# buzzer_sub_module.net
KiCad netlist of a schematic drawn in EAGLE
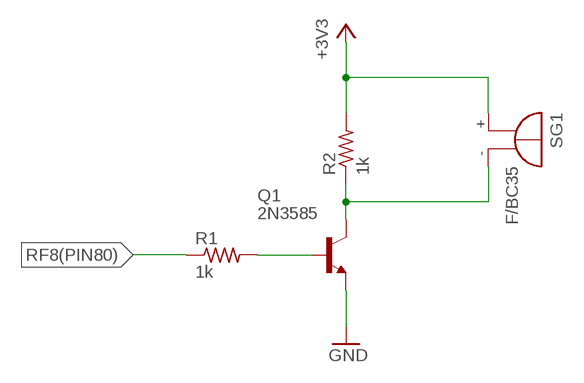
[diagram p0: schematic, sheet 1]

(export (version "E")
  (design (tool "Eeschema 10.0.6"))
  (components
    (comp (ref "Q1")
      (value "2N3585")
      (footprint "eagle-import:TO66")
      (libsource (lib "eagle-import") (part "2N3585"))
    )
    (comp (ref "R1")
      (value "1k")
      (footprint "eagle-import:0204V")
      (libsource (lib "eagle-import") (part "R-US_0204/2V"))
    )
    (comp (ref "R2")
      (value "1k")
      (footprint "eagle-import:0204V")
      (libsource (lib "eagle-import") (part "R-US_0204/2V"))
    )
    (comp (ref "SG1")
      (value "F/BC35")
      (footprint "eagle-import:F_BC35")
      (libsource (lib "eagle-import") (part "F/BC35"))
    )
  )
  (nets
    (net (code "1") (name "+3V3") (class "Default")
      (node (ref "R2") (pin "2") (pinfunction "2_2") (pintype "passive"))
      (node (ref "SG1") (pin "+") (pinfunction "+_+") (pintype "passive"))
    )
    (net (code "2") (name "GND") (class "Default")
      (node (ref "Q1") (pin "1") (pinfunction "E_1") (pintype "passive"))
    )
    (net (code "3") (name "Net-(Q1-B)") (class "Default")
      (node (ref "Q1") (pin "2") (pinfunction "B_2") (pintype "passive"))
      (node (ref "R1") (pin "2") (pinfunction "2_2") (pintype "passive"))
    )
    (net (code "4") (name "Net-(Q1-C-Pad3)") (class "Default")
      (node (ref "Q1") (pin "3") (pinfunction "C_3") (pintype "passive"))
      (node (ref "Q1") (pin "TO66") (pinfunction "C_TO66") (pintype "passive"))
      (node (ref "R2") (pin "1") (pinfunction "1_1") (pintype "passive"))
      (node (ref "SG1") (pin "-") (pinfunction "-_-") (pintype "passive"))
    )
    (net (code "5") (name "RF8(PIN80)") (class "Default")
      (node (ref "R1") (pin "1") (pinfunction "1_1") (pintype "passive"))
    )
  )
)
